# SCH_Teensy_CNC_v2_2023-01-18.net
KiCad netlist of a schematic drawn in EasyEDA
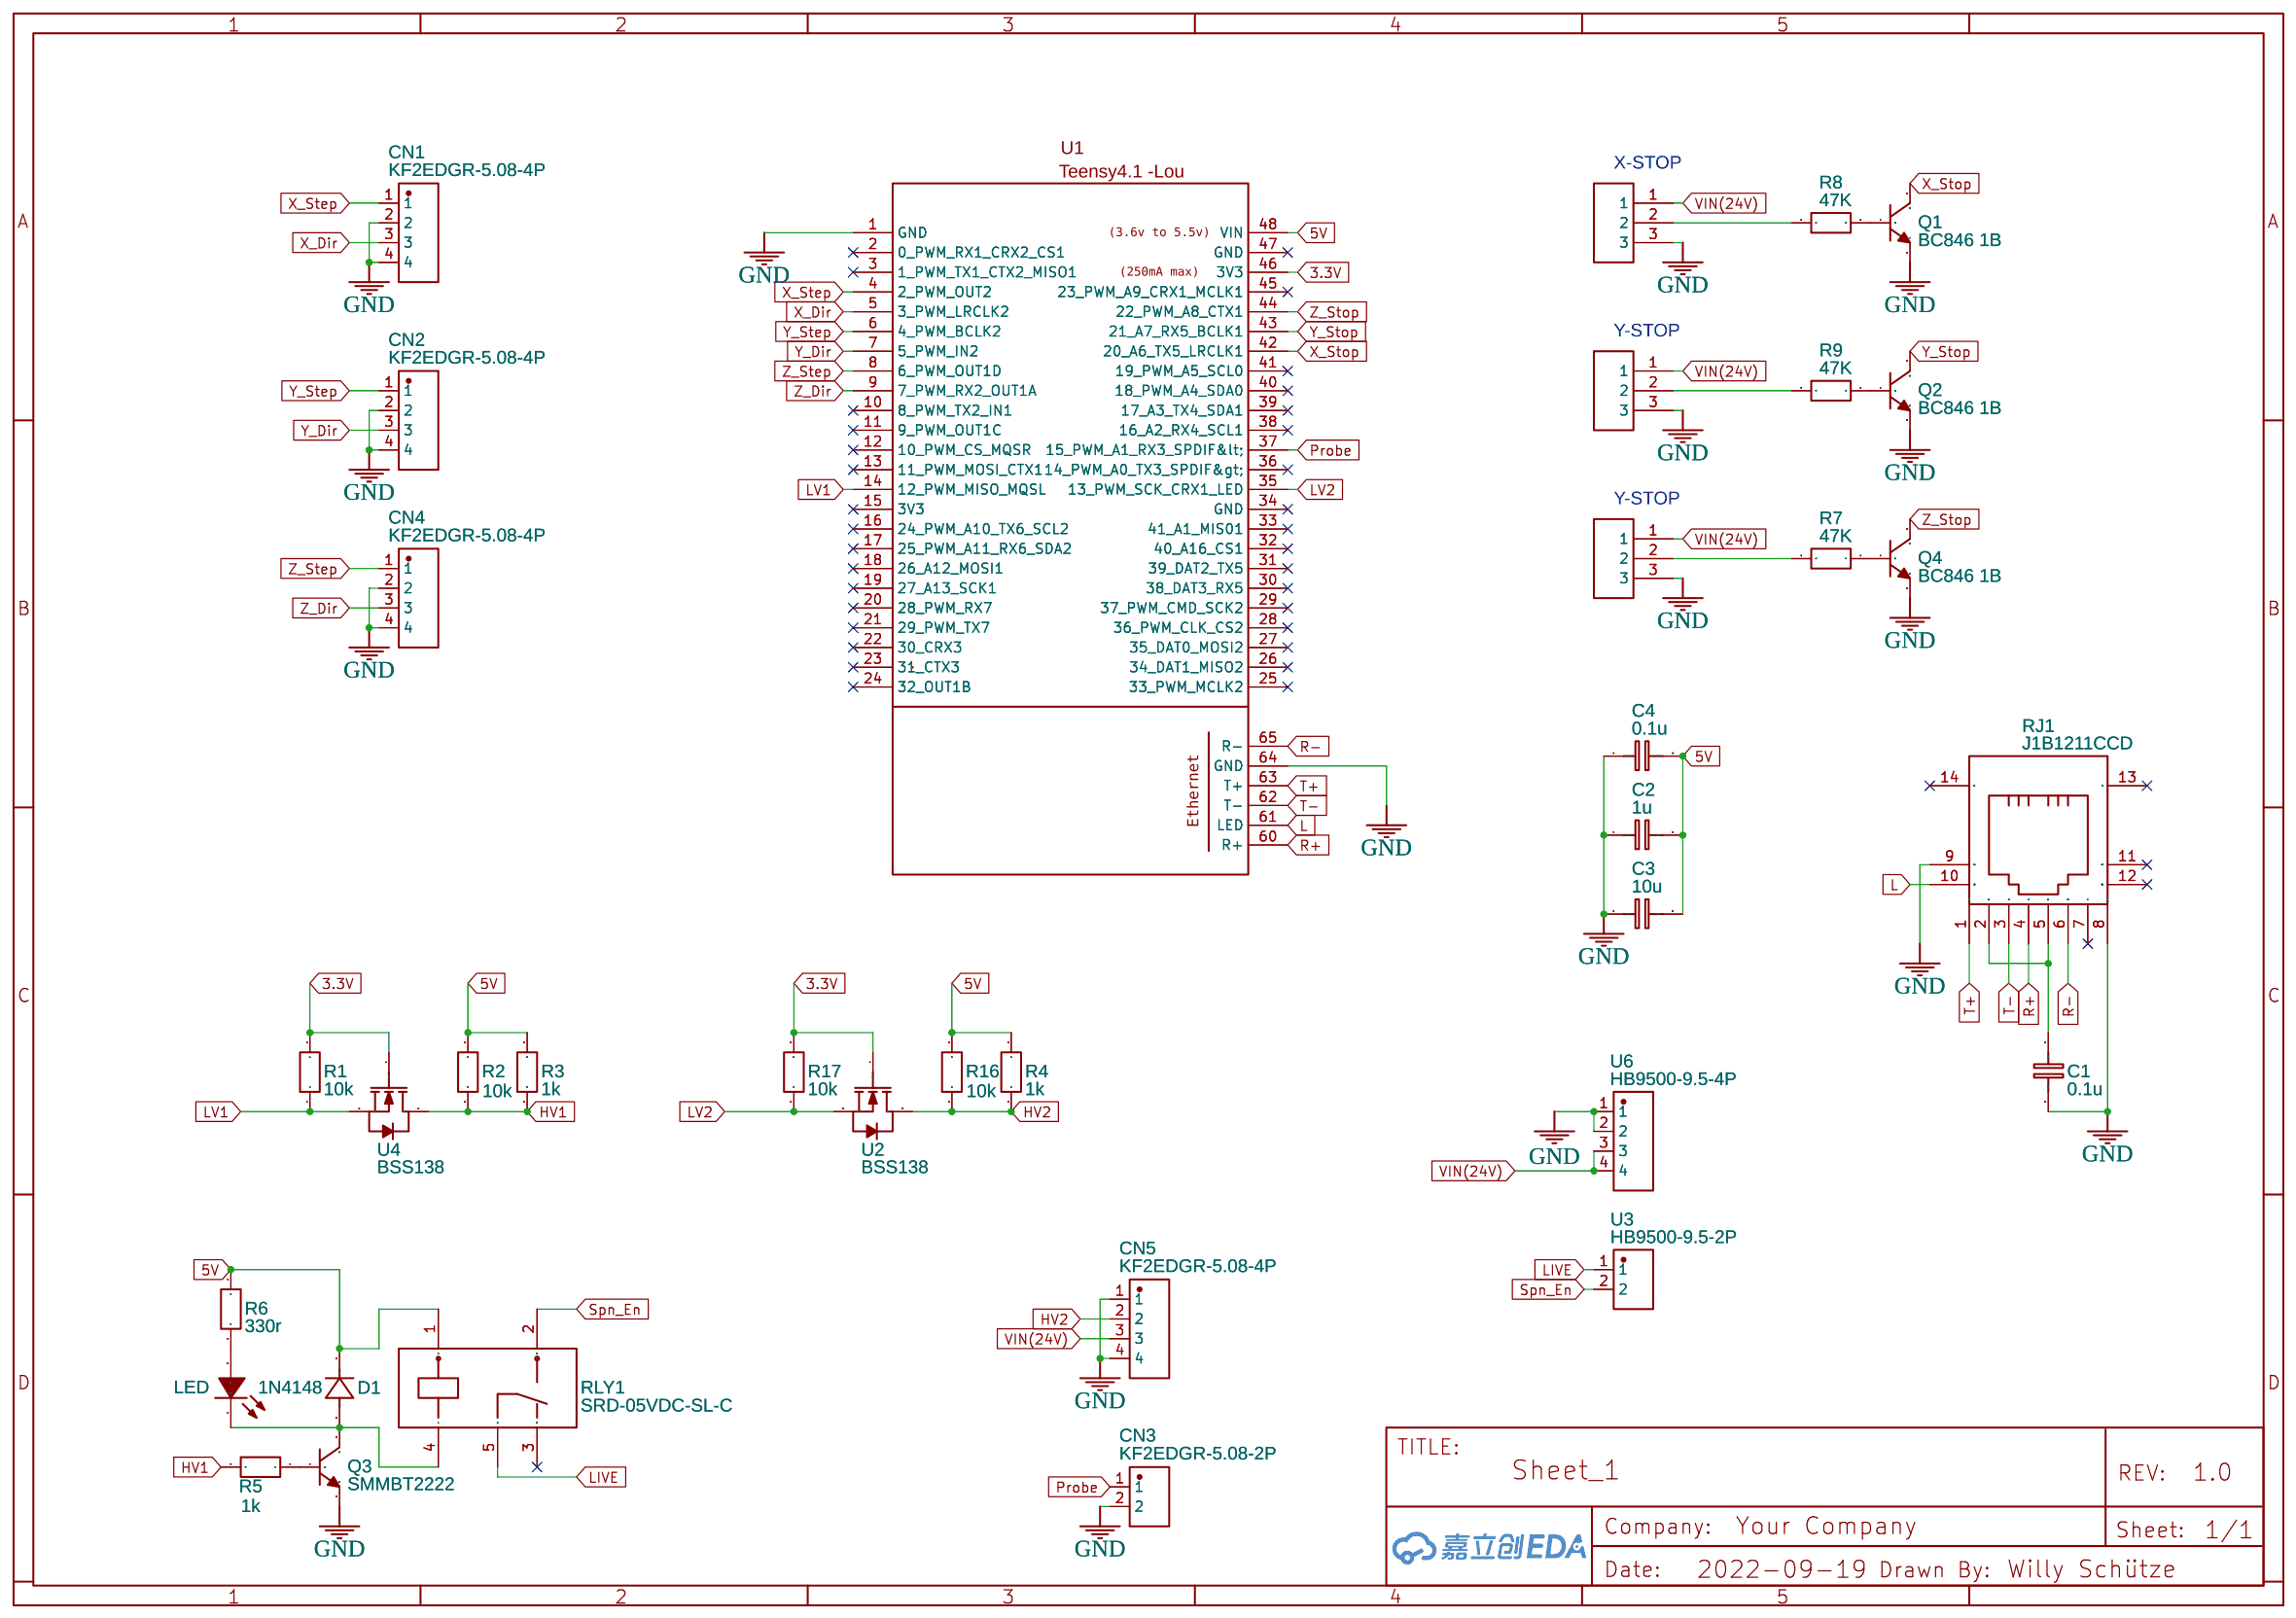
[diagram p0: schematic sheet]

(export (version "E")
  (design (tool "Eeschema 10.0.6"))
  (components
    (comp (ref "C1") (value "0.1u") (libsource (lib "") (part "C_1206_EU_1")))
    (comp (ref "C2") (value "1u") (libsource (lib "") (part "C_1206_EU")))
    (comp (ref "C3") (value "10u") (libsource (lib "") (part "C_1206_EU")))
    (comp (ref "C4") (value "0.1u") (libsource (lib "") (part "C_1206_EU")))
    (comp (ref "CN1")
      (value "KF2EDGR-5.08-4P")
      (fields (field (name "BOM_Supplier Part") "C441206"))
      (libsource (lib "") (part "KF2EDGR-5.08-4P"))
    )
    (comp (ref "CN2")
      (value "KF2EDGR-5.08-4P")
      (fields (field (name "BOM_Supplier Part") "C441206"))
      (libsource (lib "") (part "KF2EDGR-5.08-4P"))
    )
    (comp (ref "CN3")
      (value "KF2EDGR-5.08-2P")
      (fields (field (name "BOM_Supplier Part") "C441204"))
      (libsource (lib "") (part "KF2EDGR-5.08-2P"))
    )
    (comp (ref "CN4")
      (value "KF2EDGR-5.08-4P")
      (fields (field (name "BOM_Supplier Part") "C441206"))
      (libsource (lib "") (part "KF2EDGR-5.08-4P"))
    )
    (comp (ref "CN5")
      (value "KF2EDGR-5.08-4P")
      (fields (field (name "BOM_Supplier Part") "C441206"))
      (libsource (lib "") (part "KF2EDGR-5.08-4P"))
    )
    (comp (ref "D1")
      (value "1N4148")
      (fields
        (field (name "BOM_Manufacturer Part") "1N4148SOD-123")
        (field (name "BOM_Supplier Part") "C2972760")
      )
      (libsource (lib "") (part "1N4148SOD-123"))
    )
    (comp (ref "LED")
      (value "1206 LED Fab Lab UCAL")
      (fields (field (name "BOM_Manufacturer Part") "1206 LED") (field (name "BOM_Supplier Part") "1206"))
      (libsource (lib "") (part "1206 LED Fab Lab UCAL"))
    )
    (comp (ref "Q1")
      (value "BC846 1B")
      (fields (field (name "BOM_Supplier Part") "C8573"))
      (libsource (lib "") (part "BC846 1B"))
    )
    (comp (ref "Q2")
      (value "BC846 1B")
      (fields (field (name "BOM_Supplier Part") "C8573"))
      (libsource (lib "") (part "BC846 1B"))
    )
    (comp (ref "Q3")
      (value "SMMBT2222")
      (fields
        (field (name "BOM_Manufacturer Part") "SMMBT2222ALT1G")
        (field (name "BOM_Supplier Part") "C604704")
      )
      (libsource (lib "") (part "SMMBT2222ALT1G"))
    )
    (comp (ref "Q4")
      (value "BC846 1B")
      (fields (field (name "BOM_Supplier Part") "C8573"))
      (libsource (lib "") (part "BC846 1B"))
    )
    (comp (ref "R1") (value "10k") (libsource (lib "") (part "R_1206_EU")))
    (comp (ref "R2") (value "10k") (libsource (lib "") (part "R_1206_EU")))
    (comp (ref "R3") (value "1k") (libsource (lib "") (part "R_1206_EU")))
    (comp (ref "R4") (value "1k") (libsource (lib "") (part "R_1206_EU")))
    (comp (ref "R5") (value "1k") (libsource (lib "") (part "R_1206_EU_1")))
    (comp (ref "R6") (value "330r") (libsource (lib "") (part "R_1206_EU_2")))
    (comp (ref "R7") (value "47K") (libsource (lib "") (part "R_1206_EU_1")))
    (comp (ref "R8") (value "47K") (libsource (lib "") (part "R_1206_EU_1")))
    (comp (ref "R9") (value "47K") (libsource (lib "") (part "R_1206_EU_1")))
    (comp (ref "R16") (value "10k") (libsource (lib "") (part "R_1206_EU")))
    (comp (ref "R17") (value "10k") (libsource (lib "") (part "R_1206_EU")))
    (comp (ref "RJ1")
      (value "J1B1211CCD")
      (fields (field (name "BOM_Supplier Part") "C910371"))
      (libsource (lib "") (part "J1B1211CCD"))
    )
    (comp (ref "RLY1")
      (value "SRD-05VDC-SL-C")
      (fields (field (name "BOM_Supplier Part") "C35449"))
      (libsource (lib "") (part "SRD-05VDC-SL-C"))
    )
    (comp (ref "U1") (value "JST-XH-03") (libsource (lib "") (part "JST-XH-03")))
    (comp (ref "U2")
      (value "BSS138")
      (fields
        (field (name "BOM_Manufacturer Part") "BSS138LT7G")
        (field (name "BOM_Supplier Part") "C894772")
      )
      (libsource (lib "") (part "BSS138LT7G"))
    )
    (comp (ref "U3")
      (value "HB9500-9.5-2P")
      (fields (field (name "BOM_Supplier Part") "C707836"))
      (libsource (lib "") (part "HB9500-9.5-2P"))
    )
    (comp (ref "U4")
      (value "BSS138")
      (fields
        (field (name "BOM_Manufacturer Part") "BSS138LT7G")
        (field (name "BOM_Supplier Part") "C894772")
      )
      (libsource (lib "") (part "BSS138LT7G"))
    )
    (comp (ref "U5")
      (value "Teensy4.1 - WS3")
      (fields (field (name "BOM_Manufacturer Part") "Teensy4.1"))
      (libsource (lib "") (part "Teensy4.1 - WS3"))
    )
    (comp (ref "U6")
      (value "HB9500-9.5-4P")
      (fields (field (name "BOM_Supplier Part") "C707838"))
      (libsource (lib "") (part "HB9500-9.5-4P"))
    )
    (comp (ref "U8") (value "JST-XH-03") (libsource (lib "") (part "JST-XH-03")))
    (comp (ref "U9") (value "JST-XH-03") (libsource (lib "") (part "JST-XH-03")))
  )
  (nets
    (net (code "1") (name "3.3V") (class "Default")
      (node (ref "R1") (pin "2") (pinfunction "2_2") (pintype "unspecified"))
      (node (ref "R17") (pin "2") (pinfunction "2_2") (pintype "unspecified"))
      (node (ref "U2") (pin "1") (pinfunction "G_1") (pintype "unspecified"))
      (node (ref "U4") (pin "1") (pinfunction "G_1") (pintype "unspecified"))
      (node (ref "U5") (pin "46") (pinfunction "3V3_46") (pintype "bidirectional"))
    )
    (net (code "2") (name "5V") (class "Default")
      (node (ref "C2") (pin "2") (pinfunction "2_2") (pintype "unspecified"))
      (node (ref "C3") (pin "2") (pinfunction "2_2") (pintype "unspecified"))
      (node (ref "C4") (pin "2") (pinfunction "2_2") (pintype "unspecified"))
      (node (ref "D1") (pin "1") (pinfunction "K_1") (pintype "unspecified"))
      (node (ref "R16") (pin "2") (pinfunction "2_2") (pintype "unspecified"))
      (node (ref "R2") (pin "2") (pinfunction "2_2") (pintype "unspecified"))
      (node (ref "R3") (pin "2") (pinfunction "2_2") (pintype "unspecified"))
      (node (ref "R4") (pin "2") (pinfunction "2_2") (pintype "unspecified"))
      (node (ref "R6") (pin "1") (pinfunction "1_1") (pintype "unspecified"))
      (node (ref "RLY1") (pin "1") (pinfunction "1_1") (pintype "input"))
      (node (ref "U5") (pin "48") (pinfunction "VIN_48") (pintype "bidirectional"))
    )
    (net (code "3") (name "GND") (class "Default")
      (node (ref "C1") (pin "2") (pinfunction "2_2") (pintype "unspecified"))
      (node (ref "C2") (pin "1") (pinfunction "1_1") (pintype "unspecified"))
      (node (ref "C3") (pin "1") (pinfunction "1_1") (pintype "unspecified"))
      (node (ref "C4") (pin "1") (pinfunction "1_1") (pintype "unspecified"))
      (node (ref "CN1") (pin "2") (pinfunction "2_2") (pintype "unspecified"))
      (node (ref "CN1") (pin "4") (pinfunction "4_4") (pintype "unspecified"))
      (node (ref "CN2") (pin "2") (pinfunction "2_2") (pintype "unspecified"))
      (node (ref "CN2") (pin "4") (pinfunction "4_4") (pintype "unspecified"))
      (node (ref "CN3") (pin "2") (pinfunction "2_2") (pintype "unspecified"))
      (node (ref "CN4") (pin "2") (pinfunction "2_2") (pintype "unspecified"))
      (node (ref "CN4") (pin "4") (pinfunction "4_4") (pintype "unspecified"))
      (node (ref "CN5") (pin "1") (pinfunction "1_1") (pintype "unspecified"))
      (node (ref "CN5") (pin "4") (pinfunction "4_4") (pintype "unspecified"))
      (node (ref "Q1") (pin "2") (pinfunction "E_2") (pintype "unspecified"))
      (node (ref "Q2") (pin "2") (pinfunction "E_2") (pintype "unspecified"))
      (node (ref "Q3") (pin "2") (pinfunction "E_2") (pintype "input"))
      (node (ref "Q4") (pin "2") (pinfunction "E_2") (pintype "unspecified"))
      (node (ref "RJ1") (pin "8") (pinfunction "8_8") (pintype "unspecified"))
      (node (ref "RJ1") (pin "9") (pinfunction "LLED-_9") (pintype "unspecified"))
      (node (ref "U1") (pin "3") (pinfunction "3_3") (pintype "unspecified"))
      (node (ref "U5") (pin "1") (pinfunction "GND_1") (pintype "bidirectional"))
      (node (ref "U5") (pin "64") (pinfunction "GND_64") (pintype "bidirectional"))
      (node (ref "U6") (pin "1") (pinfunction "1_1") (pintype "unspecified"))
      (node (ref "U6") (pin "2") (pinfunction "2_2") (pintype "unspecified"))
      (node (ref "U8") (pin "3") (pinfunction "3_3") (pintype "unspecified"))
      (node (ref "U9") (pin "3") (pinfunction "3_3") (pintype "unspecified"))
    )
    (net (code "4") (name "HV1") (class "Default")
      (node (ref "R2") (pin "1") (pinfunction "1_1") (pintype "unspecified"))
      (node (ref "R3") (pin "1") (pinfunction "1_1") (pintype "unspecified"))
      (node (ref "R5") (pin "2") (pinfunction "2_2") (pintype "unspecified"))
      (node (ref "U4") (pin "3") (pinfunction "D_3") (pintype "unspecified"))
    )
    (net (code "5") (name "HV2") (class "Default")
      (node (ref "CN5") (pin "2") (pinfunction "2_2") (pintype "unspecified"))
      (node (ref "R16") (pin "1") (pinfunction "1_1") (pintype "unspecified"))
      (node (ref "R4") (pin "1") (pinfunction "1_1") (pintype "unspecified"))
      (node (ref "U2") (pin "3") (pinfunction "D_3") (pintype "unspecified"))
    )
    (net (code "6") (name "L") (class "Default")
      (node (ref "RJ1") (pin "10") (pinfunction "LLED+_10") (pintype "unspecified"))
      (node (ref "U5") (pin "61") (pinfunction "LED_61") (pintype "bidirectional"))
    )
    (net (code "7") (name "LIVE") (class "Default")
      (node (ref "RLY1") (pin "5") (pinfunction "5_5") (pintype "input"))
      (node (ref "U3") (pin "1") (pinfunction "1_1") (pintype "unspecified"))
    )
    (net (code "8") (name "LV1") (class "Default")
      (node (ref "R1") (pin "1") (pinfunction "1_1") (pintype "unspecified"))
      (node (ref "U4") (pin "2") (pinfunction "S_2") (pintype "unspecified"))
      (node (ref "U5") (pin "14") (pinfunction "12_PWM_MISO_MQSL_14") (pintype "bidirectional"))
    )
    (net (code "9") (name "LV2") (class "Default")
      (node (ref "R17") (pin "1") (pinfunction "1_1") (pintype "unspecified"))
      (node (ref "U2") (pin "2") (pinfunction "S_2") (pintype "unspecified"))
      (node (ref "U5") (pin "35") (pinfunction "13_PWM_SCK_CRX1_LED_35") (pintype "bidirectional"))
    )
    (net (code "10") (name "Net-(C1-Pad1)") (class "Default")
      (node (ref "C1") (pin "1") (pinfunction "1_1") (pintype "unspecified"))
      (node (ref "RJ1") (pin "2") (pinfunction "2_2") (pintype "unspecified"))
      (node (ref "RJ1") (pin "5") (pinfunction "5_5") (pintype "unspecified"))
    )
    (net (code "11") (name "Net-(D1-A)") (class "Default")
      (node (ref "D1") (pin "2") (pinfunction "A_2") (pintype "unspecified"))
      (node (ref "LED") (pin "1") (pinfunction "K_1") (pintype "unspecified"))
      (node (ref "Q3") (pin "3") (pinfunction "C_3") (pintype "input"))
      (node (ref "RLY1") (pin "4") (pinfunction "4_4") (pintype "input"))
    )
    (net (code "12") (name "Net-(LED-A)") (class "Default")
      (node (ref "LED") (pin "2") (pinfunction "A_2") (pintype "unspecified"))
      (node (ref "R6") (pin "2") (pinfunction "2_2") (pintype "unspecified"))
    )
    (net (code "13") (name "Net-(Q1-B)") (class "Default")
      (node (ref "Q1") (pin "1") (pinfunction "B_1") (pintype "unspecified"))
      (node (ref "R8") (pin "1") (pinfunction "1_1") (pintype "unspecified"))
    )
    (net (code "14") (name "Net-(Q2-B)") (class "Default")
      (node (ref "Q2") (pin "1") (pinfunction "B_1") (pintype "unspecified"))
      (node (ref "R9") (pin "1") (pinfunction "1_1") (pintype "unspecified"))
    )
    (net (code "15") (name "Net-(Q3-B)") (class "Default")
      (node (ref "Q3") (pin "1") (pinfunction "B_1") (pintype "input"))
      (node (ref "R5") (pin "1") (pinfunction "1_1") (pintype "unspecified"))
    )
    (net (code "16") (name "Net-(Q4-B)") (class "Default")
      (node (ref "Q4") (pin "1") (pinfunction "B_1") (pintype "unspecified"))
      (node (ref "R7") (pin "1") (pinfunction "1_1") (pintype "unspecified"))
    )
    (net (code "17") (name "Net-(R7-Pad2)") (class "Default")
      (node (ref "R7") (pin "2") (pinfunction "2_2") (pintype "unspecified"))
      (node (ref "U1") (pin "2") (pinfunction "2_2") (pintype "unspecified"))
    )
    (net (code "18") (name "Net-(R8-Pad2)") (class "Default")
      (node (ref "R8") (pin "2") (pinfunction "2_2") (pintype "unspecified"))
      (node (ref "U9") (pin "2") (pinfunction "2_2") (pintype "unspecified"))
    )
    (net (code "19") (name "Net-(R9-Pad2)") (class "Default")
      (node (ref "R9") (pin "2") (pinfunction "2_2") (pintype "unspecified"))
      (node (ref "U8") (pin "2") (pinfunction "2_2") (pintype "unspecified"))
    )
    (net (code "20") (name "Probe") (class "Default")
      (node (ref "CN3") (pin "1") (pinfunction "1_1") (pintype "unspecified"))
      (node (ref "U5") (pin "37") (pinfunction "15_PWM_A1_RX3_SPDIF&lt;_37") (pintype "bidirectional"))
    )
    (net (code "21") (name "R+") (class "Default")
      (node (ref "RJ1") (pin "4") (pinfunction "4_4") (pintype "unspecified"))
      (node (ref "U5") (pin "60") (pinfunction "R+_60") (pintype "bidirectional"))
    )
    (net (code "22") (name "R-") (class "Default")
      (node (ref "RJ1") (pin "6") (pinfunction "6_6") (pintype "unspecified"))
      (node (ref "U5") (pin "65") (pinfunction "R-_65") (pintype "bidirectional"))
    )
    (net (code "23") (name "Spn_En") (class "Default")
      (node (ref "RLY1") (pin "2") (pinfunction "2_2") (pintype "input"))
      (node (ref "U3") (pin "2") (pinfunction "2_2") (pintype "unspecified"))
    )
    (net (code "24") (name "T+") (class "Default")
      (node (ref "RJ1") (pin "1") (pinfunction "1_1") (pintype "unspecified"))
      (node (ref "U5") (pin "63") (pinfunction "T+_63") (pintype "bidirectional"))
    )
    (net (code "25") (name "T-") (class "Default")
      (node (ref "RJ1") (pin "3") (pinfunction "3_3") (pintype "unspecified"))
      (node (ref "U5") (pin "62") (pinfunction "T-_62") (pintype "bidirectional"))
    )
    (net (code "26") (name "VIN(24V)") (class "Default")
      (node (ref "CN5") (pin "3") (pinfunction "3_3") (pintype "unspecified"))
      (node (ref "U1") (pin "1") (pinfunction "1_1") (pintype "unspecified"))
      (node (ref "U6") (pin "3") (pinfunction "3_3") (pintype "unspecified"))
      (node (ref "U6") (pin "4") (pinfunction "4_4") (pintype "unspecified"))
      (node (ref "U8") (pin "1") (pinfunction "1_1") (pintype "unspecified"))
      (node (ref "U9") (pin "1") (pinfunction "1_1") (pintype "unspecified"))
    )
    (net (code "27") (name "X_Dir") (class "Default")
      (node (ref "CN1") (pin "3") (pinfunction "3_3") (pintype "unspecified"))
      (node (ref "U5") (pin "5") (pinfunction "3_PWM_LRCLK2_5") (pintype "bidirectional"))
    )
    (net (code "28") (name "X_Step") (class "Default")
      (node (ref "CN1") (pin "1") (pinfunction "1_1") (pintype "unspecified"))
      (node (ref "U5") (pin "4") (pinfunction "2_PWM_OUT2_4") (pintype "bidirectional"))
    )
    (net (code "29") (name "X_Stop") (class "Default")
      (node (ref "Q1") (pin "3") (pinfunction "C_3") (pintype "unspecified"))
      (node (ref "U5") (pin "42") (pinfunction "20_A6_TX5_LRCLK1_42") (pintype "bidirectional"))
    )
    (net (code "30") (name "Y_Dir") (class "Default")
      (node (ref "CN2") (pin "3") (pinfunction "3_3") (pintype "unspecified"))
      (node (ref "U5") (pin "7") (pinfunction "5_PWM_IN2_7") (pintype "bidirectional"))
    )
    (net (code "31") (name "Y_Step") (class "Default")
      (node (ref "CN2") (pin "1") (pinfunction "1_1") (pintype "unspecified"))
      (node (ref "U5") (pin "6") (pinfunction "4_PWM_BCLK2_6") (pintype "bidirectional"))
    )
    (net (code "32") (name "Y_Stop") (class "Default")
      (node (ref "Q2") (pin "3") (pinfunction "C_3") (pintype "unspecified"))
      (node (ref "U5") (pin "43") (pinfunction "21_A7_RX5_BCLK1_43") (pintype "bidirectional"))
    )
    (net (code "33") (name "Z_Dir") (class "Default")
      (node (ref "CN4") (pin "3") (pinfunction "3_3") (pintype "unspecified"))
      (node (ref "U5") (pin "9") (pinfunction "7_PWM_RX2_OUT1A_9") (pintype "bidirectional"))
    )
    (net (code "34") (name "Z_Step") (class "Default")
      (node (ref "CN4") (pin "1") (pinfunction "1_1") (pintype "unspecified"))
      (node (ref "U5") (pin "8") (pinfunction "6_PWM_OUT1D_8") (pintype "bidirectional"))
    )
    (net (code "35") (name "Z_Stop") (class "Default")
      (node (ref "Q4") (pin "3") (pinfunction "C_3") (pintype "unspecified"))
      (node (ref "U5") (pin "44") (pinfunction "22_PWM_A8_CTX1_44") (pintype "bidirectional"))
    )
    (net (code "36") (name "unconnected-(RJ1-GND-Pad13)") (class "Default")
      (node (ref "RJ1") (pin "13") (pinfunction "GND_13") (pintype "unspecified+no_connect"))
    )
    (net (code "37") (name "unconnected-(RJ1-GND-Pad14)") (class "Default")
      (node (ref "RJ1") (pin "14") (pinfunction "GND_14") (pintype "unspecified+no_connect"))
    )
    (net (code "38") (name "unconnected-(RJ1-Pad7)") (class "Default")
      (node (ref "RJ1") (pin "7") (pinfunction "7_7") (pintype "unspecified+no_connect"))
    )
    (net (code "39") (name "unconnected-(RJ1-RLED+-Pad12)") (class "Default")
      (node (ref "RJ1") (pin "12") (pinfunction "RLED+_12") (pintype "unspecified+no_connect"))
    )
    (net (code "40") (name "unconnected-(RJ1-RLED--Pad11)") (class "Default")
      (node (ref "RJ1") (pin "11") (pinfunction "RLED-_11") (pintype "unspecified+no_connect"))
    )
    (net (code "41") (name "unconnected-(RLY1-Pad3)") (class "Default")
      (node (ref "RLY1") (pin "3") (pinfunction "3_3") (pintype "input+no_connect"))
    )
    (net (code "42") (name "unconnected-(U5-0_PWM_RX1_CRX2_CS1-Pad2)") (class "Default")
      (node (ref "U5") (pin "2") (pinfunction "0_PWM_RX1_CRX2_CS1_2") (pintype "bidirectional+no_connect"))
    )
    (net (code "43") (name "unconnected-(U5-1_PWM_TX1_CTX2_MISO1-Pad3)") (class "Default")
      (node (ref "U5") (pin "3") (pinfunction "1_PWM_TX1_CTX2_MISO1_3") (pintype "bidirectional+no_connect"))
    )
    (net (code "44") (name "unconnected-(U5-3V3-Pad15)") (class "Default")
      (node (ref "U5") (pin "15") (pinfunction "3V3_15") (pintype "bidirectional+no_connect"))
    )
    (net (code "45") (name "unconnected-(U5-8_PWM_TX2_IN1-Pad10)") (class "Default")
      (node (ref "U5") (pin "10") (pinfunction "8_PWM_TX2_IN1_10") (pintype "bidirectional+no_connect"))
    )
    (net (code "46") (name "unconnected-(U5-9_PWM_OUT1C-Pad11)") (class "Default")
      (node (ref "U5") (pin "11") (pinfunction "9_PWM_OUT1C_11") (pintype "bidirectional+no_connect"))
    )
    (net (code "47") (name "unconnected-(U5-10_PWM_CS_MQSR-Pad12)") (class "Default")
      (node (ref "U5") (pin "12") (pinfunction "10_PWM_CS_MQSR_12") (pintype "bidirectional+no_connect"))
    )
    (net (code "48") (name "unconnected-(U5-11_PWM_MOSI_CTX1-Pad13)") (class "Default")
      (node (ref "U5") (pin "13") (pinfunction "11_PWM_MOSI_CTX1_13") (pintype "bidirectional+no_connect"))
    )
    (net (code "49") (name "unconnected-(U5-14_PWM_A0_TX3_SPDIF&gt;-Pad36)") (class "Default")
      (node (ref "U5") (pin "36") (pinfunction "14_PWM_A0_TX3_SPDIF&gt;_36") (pintype "bidirectional+no_connect"))
    )
    (net (code "50") (name "unconnected-(U5-16_A2_RX4_SCL1-Pad38)") (class "Default")
      (node (ref "U5") (pin "38") (pinfunction "16_A2_RX4_SCL1_38") (pintype "bidirectional+no_connect"))
    )
    (net (code "51") (name "unconnected-(U5-17_A3_TX4_SDA1-Pad39)") (class "Default")
      (node (ref "U5") (pin "39") (pinfunction "17_A3_TX4_SDA1_39") (pintype "bidirectional+no_connect"))
    )
    (net (code "52") (name "unconnected-(U5-18_PWM_A4_SDA0-Pad40)") (class "Default")
      (node (ref "U5") (pin "40") (pinfunction "18_PWM_A4_SDA0_40") (pintype "bidirectional+no_connect"))
    )
    (net (code "53") (name "unconnected-(U5-19_PWM_A5_SCL0-Pad41)") (class "Default")
      (node (ref "U5") (pin "41") (pinfunction "19_PWM_A5_SCL0_41") (pintype "bidirectional+no_connect"))
    )
    (net (code "54") (name "unconnected-(U5-23_PWM_A9_CRX1_MCLK1-Pad45)") (class "Default")
      (node (ref "U5") (pin "45") (pinfunction "23_PWM_A9_CRX1_MCLK1_45") (pintype "bidirectional+no_connect"))
    )
    (net (code "55") (name "unconnected-(U5-24_PWM_A10_TX6_SCL2-Pad16)") (class "Default")
      (node (ref "U5") (pin "16") (pinfunction "24_PWM_A10_TX6_SCL2_16") (pintype "bidirectional+no_connect"))
    )
    (net (code "56") (name "unconnected-(U5-25_PWM_A11_RX6_SDA2-Pad17)") (class "Default")
      (node (ref "U5") (pin "17") (pinfunction "25_PWM_A11_RX6_SDA2_17") (pintype "bidirectional+no_connect"))
    )
    (net (code "57") (name "unconnected-(U5-26_A12_MOSI1-Pad18)") (class "Default")
      (node (ref "U5") (pin "18") (pinfunction "26_A12_MOSI1_18") (pintype "bidirectional+no_connect"))
    )
    (net (code "58") (name "unconnected-(U5-27_A13_SCK1-Pad19)") (class "Default")
      (node (ref "U5") (pin "19") (pinfunction "27_A13_SCK1_19") (pintype "bidirectional+no_connect"))
    )
    (net (code "59") (name "unconnected-(U5-28_PWM_RX7-Pad20)") (class "Default")
      (node (ref "U5") (pin "20") (pinfunction "28_PWM_RX7_20") (pintype "bidirectional+no_connect"))
    )
    (net (code "60") (name "unconnected-(U5-29_PWM_TX7-Pad21)") (class "Default")
      (node (ref "U5") (pin "21") (pinfunction "29_PWM_TX7_21") (pintype "bidirectional+no_connect"))
    )
    (net (code "61") (name "unconnected-(U5-30_CRX3-Pad22)") (class "Default")
      (node (ref "U5") (pin "22") (pinfunction "30_CRX3_22") (pintype "bidirectional+no_connect"))
    )
    (net (code "62") (name "unconnected-(U5-31_CTX3-Pad23)") (class "Default")
      (node (ref "U5") (pin "23") (pinfunction "31_CTX3_23") (pintype "bidirectional+no_connect"))
    )
    (net (code "63") (name "unconnected-(U5-32_OUT1B-Pad24)") (class "Default")
      (node (ref "U5") (pin "24") (pinfunction "32_OUT1B_24") (pintype "bidirectional+no_connect"))
    )
    (net (code "64") (name "unconnected-(U5-33_PWM_MCLK2-Pad25)") (class "Default")
      (node (ref "U5") (pin "25") (pinfunction "33_PWM_MCLK2_25") (pintype "bidirectional+no_connect"))
    )
    (net (code "65") (name "unconnected-(U5-34_DAT1_MISO2-Pad26)") (class "Default")
      (node (ref "U5") (pin "26") (pinfunction "34_DAT1_MISO2_26") (pintype "bidirectional+no_connect"))
    )
    (net (code "66") (name "unconnected-(U5-35_DAT0_MOSI2-Pad27)") (class "Default")
      (node (ref "U5") (pin "27") (pinfunction "35_DAT0_MOSI2_27") (pintype "bidirectional+no_connect"))
    )
    (net (code "67") (name "unconnected-(U5-36_PWM_CLK_CS2-Pad28)") (class "Default")
      (node (ref "U5") (pin "28") (pinfunction "36_PWM_CLK_CS2_28") (pintype "bidirectional+no_connect"))
    )
    (net (code "68") (name "unconnected-(U5-37_PWM_CMD_SCK2-Pad29)") (class "Default")
      (node (ref "U5") (pin "29") (pinfunction "37_PWM_CMD_SCK2_29") (pintype "bidirectional+no_connect"))
    )
    (net (code "69") (name "unconnected-(U5-38_DAT3_RX5-Pad30)") (class "Default")
      (node (ref "U5") (pin "30") (pinfunction "38_DAT3_RX5_30") (pintype "bidirectional+no_connect"))
    )
    (net (code "70") (name "unconnected-(U5-39_DAT2_TX5-Pad31)") (class "Default")
      (node (ref "U5") (pin "31") (pinfunction "39_DAT2_TX5_31") (pintype "bidirectional+no_connect"))
    )
    (net (code "71") (name "unconnected-(U5-40_A16_CS1-Pad32)") (class "Default")
      (node (ref "U5") (pin "32") (pinfunction "40_A16_CS1_32") (pintype "bidirectional+no_connect"))
    )
    (net (code "72") (name "unconnected-(U5-41_A1_MIS01-Pad33)") (class "Default")
      (node (ref "U5") (pin "33") (pinfunction "41_A1_MIS01_33") (pintype "bidirectional+no_connect"))
    )
    (net (code "73") (name "unconnected-(U5-GND-Pad34)") (class "Default")
      (node (ref "U5") (pin "34") (pinfunction "GND_34") (pintype "bidirectional+no_connect"))
    )
    (net (code "74") (name "unconnected-(U5-GND-Pad47)") (class "Default")
      (node (ref "U5") (pin "47") (pinfunction "GND_47") (pintype "bidirectional+no_connect"))
    )
  )
)
